# Motors.net
KiCad netlist of a schematic drawn in Altium Designer
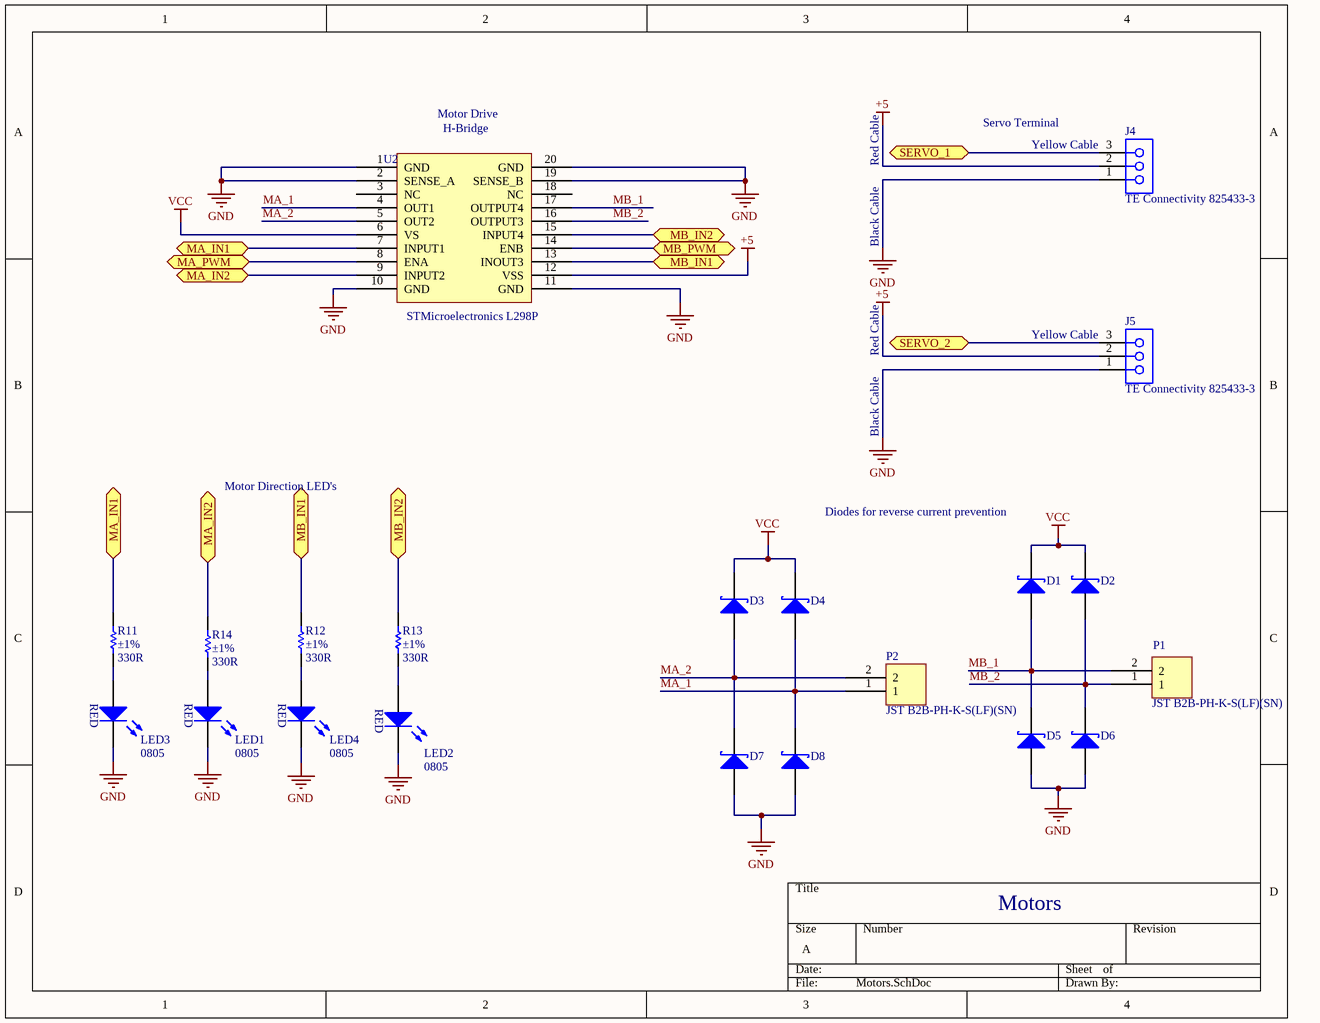
[diagram p0: Motors.SchDoc]

(export (version "E")
  (design (tool "Eeschema 10.0.6"))
  (components
    (comp (ref "D1")
      (value "SS34 SMA DO-214AC")
      (footprint "SMA")
      (description "A Schotty Barrier Rectifier")
      (libsource (lib "CommunityVault") (part "CMP-cx3sevj7k2ks0umzedmk-1"))
    )
    (comp (ref "D2")
      (value "SS34 SMA DO-214AC")
      (footprint "SMA")
      (description "A Schotty Barrier Rectifier")
      (libsource (lib "CommunityVault") (part "CMP-cx3sevj7k2ks0umzedmk-1"))
    )
    (comp (ref "D3")
      (value "SS34 SMA DO-214AC")
      (footprint "SMA")
      (description "A Schotty Barrier Rectifier")
      (libsource (lib "CommunityVault") (part "CMP-cx3sevj7k2ks0umzedmk-1"))
    )
    (comp (ref "D4")
      (value "SS34 SMA DO-214AC")
      (footprint "SMA")
      (description "A Schotty Barrier Rectifier")
      (libsource (lib "CommunityVault") (part "CMP-cx3sevj7k2ks0umzedmk-1"))
    )
    (comp (ref "D5")
      (value "SS34 SMA DO-214AC")
      (footprint "SMA")
      (description "A Schotty Barrier Rectifier")
      (libsource (lib "CommunityVault") (part "CMP-cx3sevj7k2ks0umzedmk-1"))
    )
    (comp (ref "D6")
      (value "SS34 SMA DO-214AC")
      (footprint "SMA")
      (description "A Schotty Barrier Rectifier")
      (libsource (lib "CommunityVault") (part "CMP-cx3sevj7k2ks0umzedmk-1"))
    )
    (comp (ref "D7")
      (value "SS34 SMA DO-214AC")
      (footprint "SMA")
      (description "A Schotty Barrier Rectifier")
      (libsource (lib "CommunityVault") (part "CMP-cx3sevj7k2ks0umzedmk-1"))
    )
    (comp (ref "D8")
      (value "SS34 SMA DO-214AC")
      (footprint "SMA")
      (description "A Schotty Barrier Rectifier")
      (libsource (lib "CommunityVault") (part "CMP-cx3sevj7k2ks0umzedmk-1"))
    )
    (comp (ref "J4")
      (value "TE Connectivity 825433-3")
      (footprint "PCB-43x6b8o6d5mxbq35c0sh-1")
      (description "Pin header; pin strips; AMPMODU MOD II; male; PIN: 3; straight")
      (fields (field (name "MANUFACTURER PART NUMBER") "825433-3"))
      (libsource (lib "CommunityVault") (part "CMP-52d299a8d8748d15-5"))
    )
    (comp (ref "J5")
      (value "TE Connectivity 825433-3")
      (footprint "PCB-43x6b8o6d5mxbq35c0sh-1")
      (description "Pin header; pin strips; AMPMODU MOD II; male; PIN: 3; straight")
      (fields (field (name "MANUFACTURER PART NUMBER") "825433-3"))
      (libsource (lib "CommunityVault") (part "CMP-52d299a8d8748d15-5"))
    )
    (comp (ref "LED1")
      (value "CMP-7f15b6173d91a0d2-5")
      (footprint "LED0805")
      (description "LED; SMD; 0805; red; 7.2-17mcd; 2x1.25mm; 170°; 1.8÷2.6V; 20mA")
      (fields (field (name "CASE/PACKAGE") "0805") (field (name "MANUFACTURER PART NUMBER") "HSMH-C170"))
      (libsource (lib "CommunityVault") (part "CMP-7f15b6173d91a0d2-5"))
    )
    (comp (ref "LED2")
      (value "CMP-7f15b6173d91a0d2-5")
      (footprint "LED0805")
      (description "LED; SMD; 0805; red; 7.2-17mcd; 2x1.25mm; 170°; 1.8÷2.6V; 20mA")
      (fields (field (name "CASE/PACKAGE") "0805") (field (name "MANUFACTURER PART NUMBER") "HSMH-C170"))
      (libsource (lib "CommunityVault") (part "CMP-7f15b6173d91a0d2-5"))
    )
    (comp (ref "LED3")
      (value "CMP-7f15b6173d91a0d2-5")
      (footprint "LED0805")
      (description "LED; SMD; 0805; red; 7.2-17mcd; 2x1.25mm; 170°; 1.8÷2.6V; 20mA")
      (fields (field (name "CASE/PACKAGE") "0805") (field (name "MANUFACTURER PART NUMBER") "HSMH-C170"))
      (libsource (lib "CommunityVault") (part "CMP-7f15b6173d91a0d2-5"))
    )
    (comp (ref "LED4")
      (value "CMP-7f15b6173d91a0d2-5")
      (footprint "LED0805")
      (description "LED; SMD; 0805; red; 7.2-17mcd; 2x1.25mm; 170°; 1.8÷2.6V; 20mA")
      (fields (field (name "CASE/PACKAGE") "0805") (field (name "MANUFACTURER PART NUMBER") "HSMH-C170"))
      (libsource (lib "CommunityVault") (part "CMP-7f15b6173d91a0d2-5"))
    )
    (comp (ref "P1")
      (value "JST B2B-PH-K-S(LF)(SN)")
      (footprint "PCB-gpdi66yn1jko56crxrq7-1")
      (description "PH Series 2 Position 2 mm Pitch Through Hole Top Entry Shrouded Header")
      (fields (field (name "MANUFACTURER PART NUMBER") "B2B-PH-K-S(LF)(SN)"))
      (libsource (lib "CommunityVault") (part "SYM-c32e0a272a631ce9-1"))
    )
    (comp (ref "P2")
      (value "JST B2B-PH-K-S(LF)(SN)")
      (footprint "PCB-gpdi66yn1jko56crxrq7-1")
      (description "PH Series 2 Position 2 mm Pitch Through Hole Top Entry Shrouded Header")
      (fields (field (name "MANUFACTURER PART NUMBER") "B2B-PH-K-S(LF)(SN)"))
      (libsource (lib "CommunityVault") (part "SYM-c32e0a272a631ce9-1"))
    )
    (comp (ref "R11")
      (value "Bourns CR0805-FX-4701GLF")
      (footprint "PCB-4097432-1")
      (description "Res Thick Film 0805 4.7K Ohm 1% 1/8W ±100ppm/°C Molded SMD SMD Paper Tape on Plastic Reel")
      (fields
        (field (name "MANUFACTURER PART NUMBER") "CR0805-FX-4701GLF")
        (field (name "RESISTANCE TOLERANCE") "±1%")
        (field (name "RESISTANCE") "330R")
      )
      (libsource (lib "CommunityVault") (part "CMP-97505e06006c4897-1"))
    )
    (comp (ref "R12")
      (value "Bourns CR0805-FX-4701GLF")
      (footprint "PCB-4097432-1")
      (description "Res Thick Film 0805 4.7K Ohm 1% 1/8W ±100ppm/°C Molded SMD SMD Paper Tape on Plastic Reel")
      (fields
        (field (name "MANUFACTURER PART NUMBER") "CR0805-FX-4701GLF")
        (field (name "RESISTANCE TOLERANCE") "±1%")
        (field (name "RESISTANCE") "330R")
      )
      (libsource (lib "CommunityVault") (part "CMP-97505e06006c4897-1"))
    )
    (comp (ref "R13")
      (value "Bourns CR0805-FX-4701GLF")
      (footprint "PCB-4097432-1")
      (description "Res Thick Film 0805 4.7K Ohm 1% 1/8W ±100ppm/°C Molded SMD SMD Paper Tape on Plastic Reel")
      (fields
        (field (name "MANUFACTURER PART NUMBER") "CR0805-FX-4701GLF")
        (field (name "RESISTANCE TOLERANCE") "±1%")
        (field (name "RESISTANCE") "330R")
      )
      (libsource (lib "CommunityVault") (part "CMP-97505e06006c4897-1"))
    )
    (comp (ref "R14")
      (value "Bourns CR0805-FX-4701GLF")
      (footprint "PCB-4097432-1")
      (description "Res Thick Film 0805 4.7K Ohm 1% 1/8W ±100ppm/°C Molded SMD SMD Paper Tape on Plastic Reel")
      (fields
        (field (name "MANUFACTURER PART NUMBER") "CR0805-FX-4701GLF")
        (field (name "RESISTANCE TOLERANCE") "±1%")
        (field (name "RESISTANCE") "330R")
      )
      (libsource (lib "CommunityVault") (part "CMP-97505e06006c4897-1"))
    )
    (comp (ref "U2")
      (value "STMicroelectronics L298P")
      (footprint "L298PSOIC127P1420X360-20N")
      (description "L298 Series Dual Full Bridge 4 A 46 V Driver Surface Mount - PowerSO-20")
      (fields (field (name "MANUFACTURER PART NUMBER") "L298P"))
      (libsource (lib "CommunityVault") (part "CMP-1433026-9"))
    )
  )
  (nets
    (net (code "1") (name "+5") (class "Default")
      (node (ref "J4") (pin "2") (pinfunction "2_2") (pintype "passive"))
      (node (ref "J5") (pin "2") (pinfunction "2_2") (pintype "passive"))
      (node (ref "U2") (pin "12") (pinfunction "VSS_12") (pintype "passive"))
    )
    (net (code "2") (name "/MA_1") (class "Default")
      (node (ref "D4") (pin "1") (pinfunction "A_1") (pintype "passive"))
      (node (ref "D8") (pin "2") (pinfunction "K_2") (pintype "passive"))
      (node (ref "P2") (pin "1") (pinfunction "1_1") (pintype "passive"))
      (node (ref "U2") (pin "4") (pinfunction "OUT1_4") (pintype "passive"))
    )
    (net (code "3") (name "/MA_2") (class "Default")
      (node (ref "D3") (pin "1") (pinfunction "A_1") (pintype "passive"))
      (node (ref "D7") (pin "2") (pinfunction "K_2") (pintype "passive"))
      (node (ref "P2") (pin "2") (pinfunction "2_2") (pintype "passive"))
      (node (ref "U2") (pin "5") (pinfunction "OUT2_5") (pintype "passive"))
    )
    (net (code "4") (name "/MA_IN1") (class "Default")
      (node (ref "R11") (pin "2") (pinfunction "2_2") (pintype "passive"))
      (node (ref "U2") (pin "7") (pinfunction "INPUT1_7") (pintype "passive"))
    )
    (net (code "5") (name "/MA_IN2") (class "Default")
      (node (ref "R14") (pin "2") (pinfunction "2_2") (pintype "passive"))
      (node (ref "U2") (pin "9") (pinfunction "INPUT2_9") (pintype "passive"))
    )
    (net (code "6") (name "/MA_PWM") (class "Default")
      (node (ref "U2") (pin "8") (pinfunction "ENA_8") (pintype "passive"))
    )
    (net (code "7") (name "/MB_1") (class "Default")
      (node (ref "D1") (pin "1") (pinfunction "A_1") (pintype "passive"))
      (node (ref "D5") (pin "2") (pinfunction "K_2") (pintype "passive"))
      (node (ref "P1") (pin "2") (pinfunction "2_2") (pintype "passive"))
      (node (ref "U2") (pin "17") (pinfunction "OUTPUT4_17") (pintype "passive"))
    )
    (net (code "8") (name "/MB_2") (class "Default")
      (node (ref "D2") (pin "1") (pinfunction "A_1") (pintype "passive"))
      (node (ref "D6") (pin "2") (pinfunction "K_2") (pintype "passive"))
      (node (ref "P1") (pin "1") (pinfunction "1_1") (pintype "passive"))
      (node (ref "U2") (pin "16") (pinfunction "OUTPUT3_16") (pintype "passive"))
    )
    (net (code "9") (name "/MB_IN1") (class "Default")
      (node (ref "R12") (pin "2") (pinfunction "2_2") (pintype "passive"))
      (node (ref "U2") (pin "13") (pinfunction "INOUT3_13") (pintype "passive"))
    )
    (net (code "10") (name "/MB_IN2") (class "Default")
      (node (ref "R13") (pin "2") (pinfunction "2_2") (pintype "passive"))
      (node (ref "U2") (pin "15") (pinfunction "INPUT4_15") (pintype "passive"))
    )
    (net (code "11") (name "/MB_PWM") (class "Default")
      (node (ref "U2") (pin "14") (pinfunction "ENB_14") (pintype "passive"))
    )
    (net (code "12") (name "/SERVO_1") (class "Default")
      (node (ref "J4") (pin "3") (pinfunction "3_3") (pintype "passive"))
    )
    (net (code "13") (name "/SERVO_2") (class "Default")
      (node (ref "J5") (pin "3") (pinfunction "3_3") (pintype "passive"))
    )
    (net (code "14") (name "GND") (class "Default")
      (node (ref "D5") (pin "1") (pinfunction "A_1") (pintype "passive"))
      (node (ref "D6") (pin "1") (pinfunction "A_1") (pintype "passive"))
      (node (ref "D7") (pin "1") (pinfunction "A_1") (pintype "passive"))
      (node (ref "D8") (pin "1") (pinfunction "A_1") (pintype "passive"))
      (node (ref "J4") (pin "1") (pinfunction "1_1") (pintype "passive"))
      (node (ref "J5") (pin "1") (pinfunction "1_1") (pintype "passive"))
      (node (ref "LED1") (pin "1") (pinfunction "K_1") (pintype "passive"))
      (node (ref "LED2") (pin "1") (pinfunction "K_1") (pintype "passive"))
      (node (ref "LED3") (pin "1") (pinfunction "K_1") (pintype "passive"))
      (node (ref "LED4") (pin "1") (pinfunction "K_1") (pintype "passive"))
      (node (ref "U2") (pin "1") (pinfunction "GND_1") (pintype "passive"))
      (node (ref "U2") (pin "10") (pinfunction "GND_10") (pintype "passive"))
      (node (ref "U2") (pin "11") (pinfunction "GND_11") (pintype "passive"))
      (node (ref "U2") (pin "19") (pinfunction "SENSE_B_19") (pintype "passive"))
      (node (ref "U2") (pin "2") (pinfunction "SENSE_A_2") (pintype "passive"))
      (node (ref "U2") (pin "20") (pinfunction "GND_20") (pintype "passive"))
    )
    (net (code "15") (name "Net-(LED1-A)") (class "Default")
      (node (ref "LED1") (pin "2") (pinfunction "A_2") (pintype "passive"))
      (node (ref "R14") (pin "1") (pinfunction "1_1") (pintype "passive"))
    )
    (net (code "16") (name "Net-(LED2-A)") (class "Default")
      (node (ref "LED2") (pin "2") (pinfunction "A_2") (pintype "passive"))
      (node (ref "R13") (pin "1") (pinfunction "1_1") (pintype "passive"))
    )
    (net (code "17") (name "Net-(LED3-A)") (class "Default")
      (node (ref "LED3") (pin "2") (pinfunction "A_2") (pintype "passive"))
      (node (ref "R11") (pin "1") (pinfunction "1_1") (pintype "passive"))
    )
    (net (code "18") (name "Net-(LED4-A)") (class "Default")
      (node (ref "LED4") (pin "2") (pinfunction "A_2") (pintype "passive"))
      (node (ref "R12") (pin "1") (pinfunction "1_1") (pintype "passive"))
    )
    (net (code "19") (name "VCC") (class "Default")
      (node (ref "D1") (pin "2") (pinfunction "K_2") (pintype "passive"))
      (node (ref "D2") (pin "2") (pinfunction "K_2") (pintype "passive"))
      (node (ref "D3") (pin "2") (pinfunction "K_2") (pintype "passive"))
      (node (ref "D4") (pin "2") (pinfunction "K_2") (pintype "passive"))
      (node (ref "U2") (pin "6") (pinfunction "VS_6") (pintype "passive"))
    )
    (net (code "20") (name "unconnected-(U2-NC-Pad3)") (class "Default")
      (node (ref "U2") (pin "3") (pinfunction "NC_3") (pintype "passive"))
    )
    (net (code "21") (name "unconnected-(U2-NC-Pad18)") (class "Default")
      (node (ref "U2") (pin "18") (pinfunction "NC_18") (pintype "passive"))
    )
  )
)
